# SCH_AP-Button-LED-V2_EasyEDA.net
KiCad netlist of a schematic drawn in EasyEDA
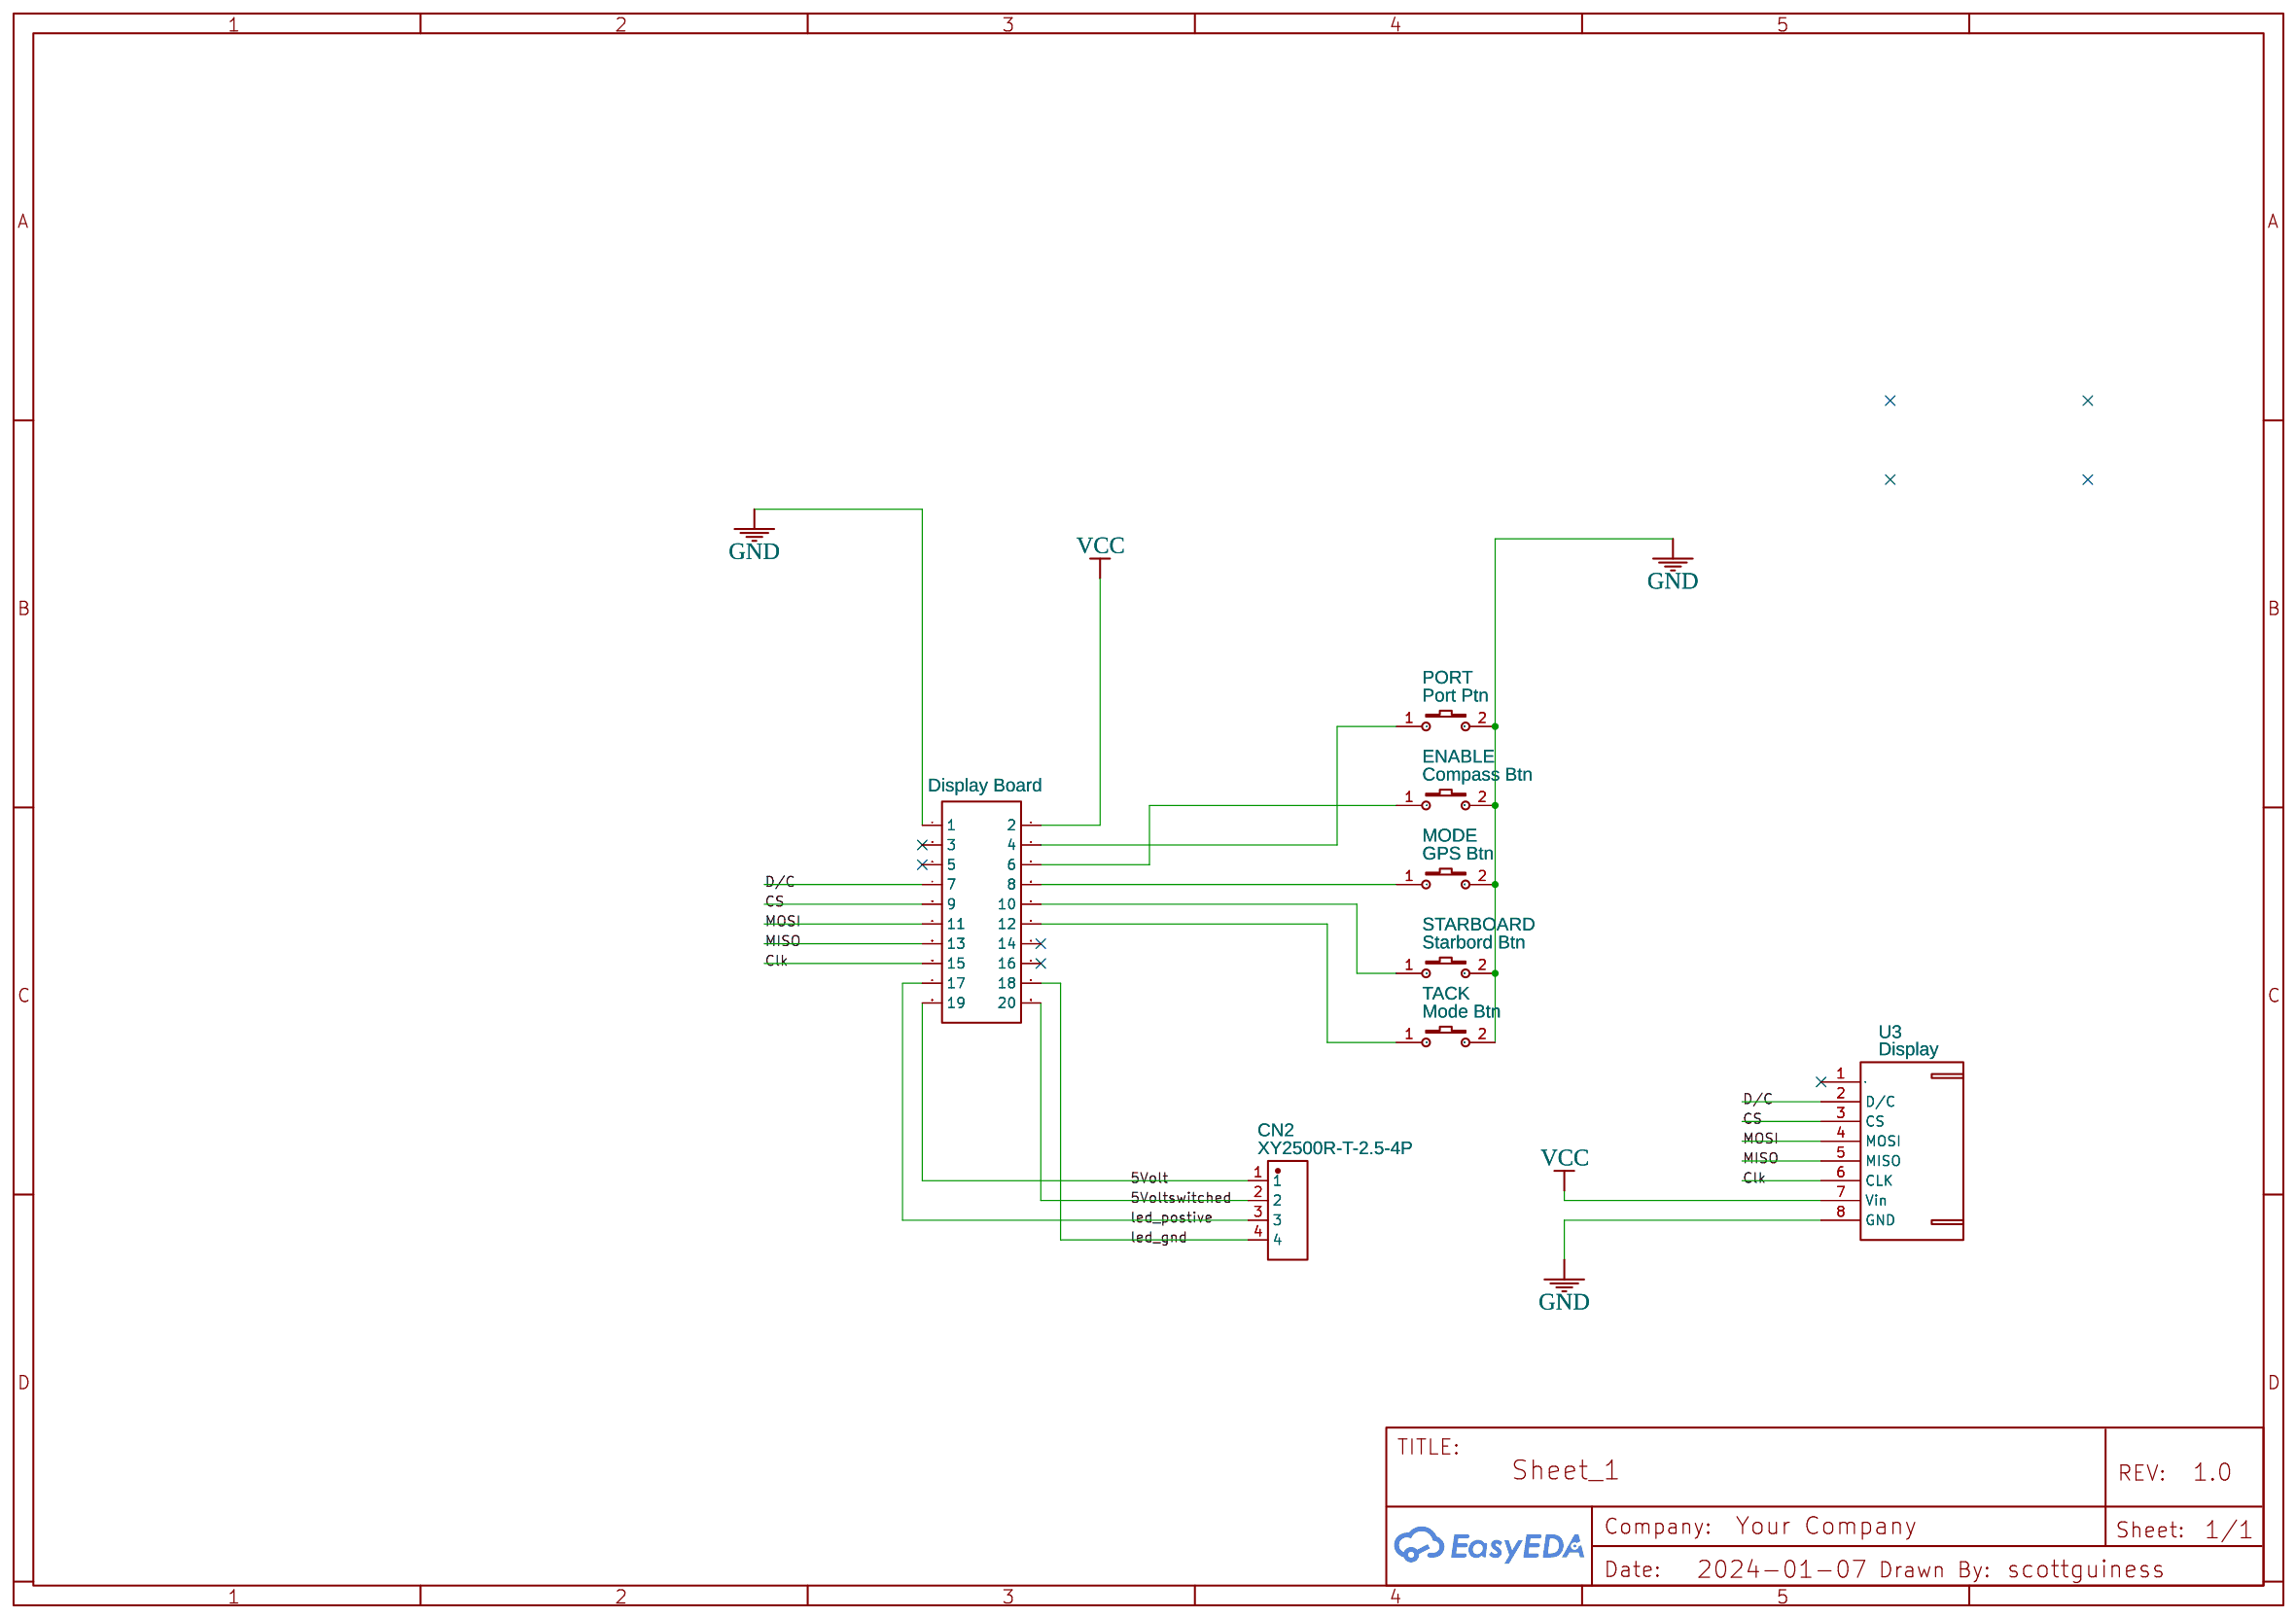
[diagram p0: schematic sheet]

(export (version "E")
  (design (tool "Eeschema 10.0.6"))
  (components
    (comp (ref "BUTTON_LED1") (value "Display Board") (libsource (lib "") (part "HDR-M-2.54_2x10")))
    (comp (ref "CN2")
      (value "XY2500R-T-2.5-4P")
      (fields (field (name "Manufacturer") "XINLAIYA(新莱亚)"))
      (libsource (lib "") (part "XY2500R-T-2.5-4P"))
    )
    (comp (ref "ENABLE")
      (value "Compass Btn")
      (fields (field (name "Manufacturer Part") "K2-1107ST-A4SW-06"))
      (libsource (lib "") (part "K2-3.6×6.1_SMD_1"))
    )
    (comp (ref "MODE")
      (value "GPS Btn")
      (fields (field (name "Manufacturer Part") "K2-1107ST-A4SW-06"))
      (libsource (lib "") (part "K2-3.6×6.1_SMD"))
    )
    (comp (ref "PORT")
      (value "Port Ptn")
      (fields (field (name "Manufacturer Part") "K2-1107ST-A4SW-06"))
      (libsource (lib "") (part "K2-3.6×6.1_SMD_2"))
    )
    (comp (ref "STARBOARD")
      (value "Starbord Btn")
      (fields (field (name "Manufacturer Part") "K2-1107ST-A4SW-06"))
      (libsource (lib "") (part "K2-3.6×6.1_SMD_4"))
    )
    (comp (ref "TACK")
      (value "Mode Btn")
      (fields (field (name "Manufacturer Part") "K2-1107ST-A4SW-06"))
      (libsource (lib "") (part "K2-3.6×6.1_SMD_3"))
    )
    (comp (ref "U3") (value "Display") (libsource (lib "") (part "JST-XH-8-Pin")))
  )
  (nets
    (net (code "1") (name "/5Volt") (class "Default")
      (node (ref "BUTTON_LED1") (pin "19") (pinfunction "19_19") (pintype "unspecified"))
      (node (ref "CN2") (pin "1") (pinfunction "1_1") (pintype "unspecified"))
    )
    (net (code "2") (name "/5Voltswitched") (class "Default")
      (node (ref "BUTTON_LED1") (pin "20") (pinfunction "20_20") (pintype "unspecified"))
      (node (ref "CN2") (pin "2") (pinfunction "2_2") (pintype "unspecified"))
    )
    (net (code "3") (name "/CS") (class "Default")
      (node (ref "BUTTON_LED1") (pin "9") (pinfunction "9_9") (pintype "unspecified"))
      (node (ref "U3") (pin "3") (pinfunction "CS_3") (pintype "unspecified"))
    )
    (net (code "4") (name "/Clk") (class "Default")
      (node (ref "BUTTON_LED1") (pin "15") (pinfunction "15_15") (pintype "unspecified"))
      (node (ref "U3") (pin "6") (pinfunction "CLK_6") (pintype "unspecified"))
    )
    (net (code "5") (name "/D{slash}C") (class "Default")
      (node (ref "BUTTON_LED1") (pin "7") (pinfunction "7_7") (pintype "unspecified"))
      (node (ref "U3") (pin "2") (pinfunction "D/C_2") (pintype "unspecified"))
    )
    (net (code "6") (name "/MISO") (class "Default")
      (node (ref "BUTTON_LED1") (pin "13") (pinfunction "13_13") (pintype "unspecified"))
      (node (ref "U3") (pin "5") (pinfunction "MISO_5") (pintype "unspecified"))
    )
    (net (code "7") (name "/MOSI") (class "Default")
      (node (ref "BUTTON_LED1") (pin "11") (pinfunction "11_11") (pintype "unspecified"))
      (node (ref "U3") (pin "4") (pinfunction "MOSI_4") (pintype "unspecified"))
    )
    (net (code "8") (name "/led_gnd") (class "Default")
      (node (ref "BUTTON_LED1") (pin "18") (pinfunction "18_18") (pintype "unspecified"))
      (node (ref "CN2") (pin "4") (pinfunction "4_4") (pintype "unspecified"))
    )
    (net (code "9") (name "/led_postive") (class "Default")
      (node (ref "BUTTON_LED1") (pin "17") (pinfunction "17_17") (pintype "unspecified"))
      (node (ref "CN2") (pin "3") (pinfunction "3_3") (pintype "unspecified"))
    )
    (net (code "10") (name "GND") (class "Default")
      (node (ref "BUTTON_LED1") (pin "1") (pinfunction "1_1") (pintype "unspecified"))
      (node (ref "ENABLE") (pin "2") (pinfunction "2_2") (pintype "unspecified"))
      (node (ref "MODE") (pin "2") (pinfunction "2_2") (pintype "unspecified"))
      (node (ref "PORT") (pin "2") (pinfunction "2_2") (pintype "unspecified"))
      (node (ref "STARBOARD") (pin "2") (pinfunction "2_2") (pintype "unspecified"))
      (node (ref "TACK") (pin "2") (pinfunction "2_2") (pintype "unspecified"))
      (node (ref "U3") (pin "8") (pinfunction "GND_8") (pintype "unspecified"))
    )
    (net (code "11") (name "Net-(BUTTON_LED1-Pad4)") (class "Default")
      (node (ref "BUTTON_LED1") (pin "4") (pinfunction "4_4") (pintype "unspecified"))
      (node (ref "PORT") (pin "1") (pinfunction "1_1") (pintype "unspecified"))
    )
    (net (code "12") (name "Net-(BUTTON_LED1-Pad6)") (class "Default")
      (node (ref "BUTTON_LED1") (pin "6") (pinfunction "6_6") (pintype "unspecified"))
      (node (ref "ENABLE") (pin "1") (pinfunction "1_1") (pintype "unspecified"))
    )
    (net (code "13") (name "Net-(BUTTON_LED1-Pad8)") (class "Default")
      (node (ref "BUTTON_LED1") (pin "8") (pinfunction "8_8") (pintype "unspecified"))
      (node (ref "MODE") (pin "1") (pinfunction "1_1") (pintype "unspecified"))
    )
    (net (code "14") (name "Net-(BUTTON_LED1-Pad10)") (class "Default")
      (node (ref "BUTTON_LED1") (pin "10") (pinfunction "10_10") (pintype "unspecified"))
      (node (ref "STARBOARD") (pin "1") (pinfunction "1_1") (pintype "unspecified"))
    )
    (net (code "15") (name "Net-(BUTTON_LED1-Pad12)") (class "Default")
      (node (ref "BUTTON_LED1") (pin "12") (pinfunction "12_12") (pintype "unspecified"))
      (node (ref "TACK") (pin "1") (pinfunction "1_1") (pintype "unspecified"))
    )
    (net (code "16") (name "VCC") (class "Default")
      (node (ref "BUTTON_LED1") (pin "2") (pinfunction "2_2") (pintype "unspecified"))
      (node (ref "U3") (pin "7") (pinfunction "Vin_7") (pintype "unspecified"))
    )
    (net (code "17") (name "unconnected-(BUTTON_LED1-Pad3)") (class "Default")
      (node (ref "BUTTON_LED1") (pin "3") (pinfunction "3_3") (pintype "unspecified+no_connect"))
    )
    (net (code "18") (name "unconnected-(BUTTON_LED1-Pad5)") (class "Default")
      (node (ref "BUTTON_LED1") (pin "5") (pinfunction "5_5") (pintype "unspecified+no_connect"))
    )
    (net (code "19") (name "unconnected-(BUTTON_LED1-Pad14)") (class "Default")
      (node (ref "BUTTON_LED1") (pin "14") (pinfunction "14_14") (pintype "unspecified+no_connect"))
    )
    (net (code "20") (name "unconnected-(BUTTON_LED1-Pad16)") (class "Default")
      (node (ref "BUTTON_LED1") (pin "16") (pinfunction "16_16") (pintype "unspecified+no_connect"))
    )
    (net (code "21") (name "unconnected-(U3-Pad1)") (class "Default")
      (node (ref "U3") (pin "1") (pinfunction "1_1") (pintype "unspecified+no_connect"))
    )
  )
)
